# usb_serial.net
KiCad netlist of a schematic drawn in EAGLE
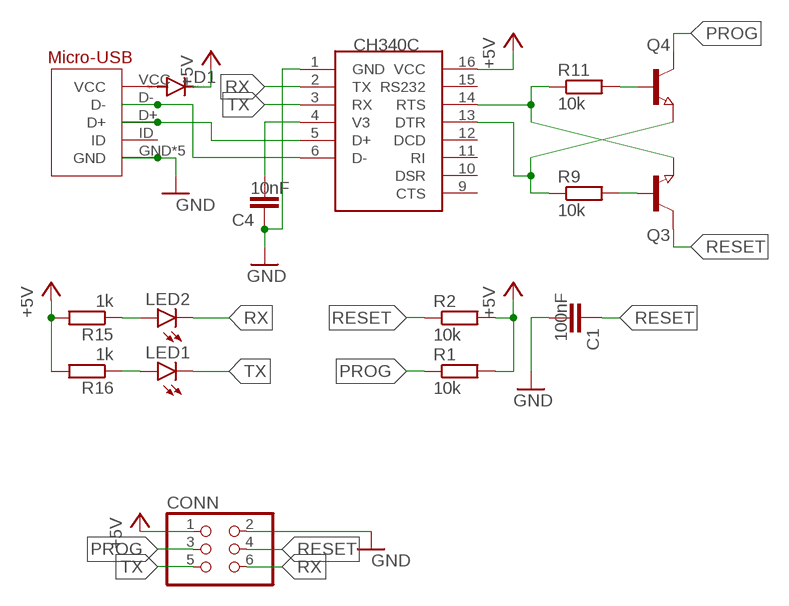
[diagram p0: schematic, sheet 1]

(export (version "E")
  (design (tool "Eeschema 10.0.6"))
  (components
    (comp (ref "C1")
      (value "100nF")
      (footprint "eagle-import:C0603K")
      (libsource (lib "eagle-import") (part "C-EUC0603K"))
    )
    (comp (ref "C4")
      (value "10nF")
      (footprint "eagle-import:C0603K")
      (libsource (lib "eagle-import") (part "C-EUC0603K"))
    )
    (comp (ref "CONN")
      (value "PINHD-2X3")
      (footprint "eagle-import:2X03")
      (libsource (lib "eagle-import") (part "PINHD-2X3"))
    )
    (comp (ref "D1")
      (value "DIODE-MICROMELF-R")
      (footprint "eagle-import:MICROMELF-R")
      (libsource (lib "eagle-import") (part "DIODE-MICROMELF-R"))
    )
    (comp (ref "J1")
      (value "MICRO-USB")
      (footprint "eagle-import:MICRO-USB")
      (fields
        (field (name "MANUFACTURER_PART_NUMBER") "ZX62D-B-5P8(30)")
        (field (name "COPYRIGHT") "Copyright (C) 2018 Accelerated Designs. All rights reserved")
      )
      (libsource (lib "eagle-import") (part "MICRO-USB"))
    )
    (comp (ref "LED1")
      (value "LEDCHIPLED_0805")
      (footprint "eagle-import:CHIPLED_0805")
      (libsource (lib "eagle-import") (part "LEDCHIPLED_0805"))
    )
    (comp (ref "LED2")
      (value "LEDCHIPLED_0805")
      (footprint "eagle-import:CHIPLED_0805")
      (libsource (lib "eagle-import") (part "LEDCHIPLED_0805"))
    )
    (comp (ref "Q3")
      (value "NPN-TRANSISTOR_SOT23")
      (footprint "eagle-import:SOT23")
      (libsource (lib "eagle-import") (part "NPN-TRANSISTOR_SOT23"))
    )
    (comp (ref "Q4")
      (value "NPN-TRANSISTOR_SOT23")
      (footprint "eagle-import:SOT23")
      (libsource (lib "eagle-import") (part "NPN-TRANSISTOR_SOT23"))
    )
    (comp (ref "R1")
      (value "10k")
      (footprint "eagle-import:R0603")
      (libsource (lib "eagle-import") (part "R-EU_R0603"))
    )
    (comp (ref "R2")
      (value "10k")
      (footprint "eagle-import:R0603")
      (libsource (lib "eagle-import") (part "R-EU_R0603"))
    )
    (comp (ref "R9")
      (value "10k")
      (footprint "eagle-import:R0603")
      (libsource (lib "eagle-import") (part "R-EU_R0603"))
    )
    (comp (ref "R11")
      (value "10k")
      (footprint "eagle-import:R0603")
      (libsource (lib "eagle-import") (part "R-EU_R0603"))
    )
    (comp (ref "R15")
      (value "1k")
      (footprint "eagle-import:R0603")
      (libsource (lib "eagle-import") (part "R-EU_R0603"))
    )
    (comp (ref "R16")
      (value "1k")
      (footprint "eagle-import:R0603")
      (libsource (lib "eagle-import") (part "R-EU_R0603"))
    )
    (comp (ref "U$3")
      (value "CH340C")
      (footprint "eagle-import:SOIC16")
      (libsource (lib "eagle-import") (part "CH340C"))
    )
  )
  (nets
    (net (code "1") (name "+5V") (class "Default")
      (node (ref "CONN") (pin "1") (pinfunction "1_1") (pintype "passive"))
      (node (ref "D1") (pin "C") (pinfunction "C_C") (pintype "passive"))
      (node (ref "R1") (pin "2") (pinfunction "2_2") (pintype "passive"))
      (node (ref "R15") (pin "2") (pinfunction "2_2") (pintype "passive"))
      (node (ref "R16") (pin "2") (pinfunction "2_2") (pintype "passive"))
      (node (ref "R2") (pin "2") (pinfunction "2_2") (pintype "passive"))
      (node (ref "U$3") (pin "16") (pinfunction "VCC_16") (pintype "bidirectional"))
    )
    (net (code "2") (name "GND") (class "Default")
      (node (ref "C1") (pin "2") (pinfunction "2_2") (pintype "passive"))
      (node (ref "C4") (pin "1") (pinfunction "1_1") (pintype "passive"))
      (node (ref "CONN") (pin "2") (pinfunction "2_2") (pintype "passive"))
      (node (ref "J1") (pin "GND") (pinfunction "GND_GND") (pintype "passive"))
      (node (ref "J1") (pin "GP1") (pinfunction "GND_GP1") (pintype "passive"))
      (node (ref "J1") (pin "GP2") (pinfunction "GND_GP2") (pintype "passive"))
      (node (ref "J1") (pin "GP3") (pinfunction "GND_GP3") (pintype "passive"))
      (node (ref "J1") (pin "GP4") (pinfunction "GND_GP4") (pintype "passive"))
      (node (ref "U$3") (pin "1") (pinfunction "GND_1") (pintype "bidirectional"))
    )
    (net (code "3") (name "Net-(D1-PadA)") (class "Default")
      (node (ref "D1") (pin "A") (pinfunction "A_A") (pintype "passive"))
      (node (ref "J1") (pin "VCC") (pinfunction "VCC_VCC") (pintype "passive"))
    )
    (net (code "4") (name "Net-(LED1-PadA)") (class "Default")
      (node (ref "LED1") (pin "A") (pinfunction "A_A") (pintype "passive"))
      (node (ref "R16") (pin "1") (pinfunction "1_1") (pintype "passive"))
    )
    (net (code "5") (name "Net-(LED2-PadA)") (class "Default")
      (node (ref "LED2") (pin "A") (pinfunction "A_A") (pintype "passive"))
      (node (ref "R15") (pin "1") (pinfunction "1_1") (pintype "passive"))
    )
    (net (code "6") (name "Net-(Q3-B)") (class "Default")
      (node (ref "Q3") (pin "1") (pinfunction "B_1") (pintype "passive"))
      (node (ref "R9") (pin "2") (pinfunction "2_2") (pintype "passive"))
    )
    (net (code "7") (name "Net-(Q3-E)") (class "Default")
      (node (ref "Q3") (pin "2") (pinfunction "E_2") (pintype "passive"))
      (node (ref "R11") (pin "1") (pinfunction "1_1") (pintype "passive"))
      (node (ref "U$3") (pin "14") (pinfunction "RTS_14") (pintype "bidirectional"))
    )
    (net (code "8") (name "Net-(Q4-B)") (class "Default")
      (node (ref "Q4") (pin "1") (pinfunction "B_1") (pintype "passive"))
      (node (ref "R11") (pin "2") (pinfunction "2_2") (pintype "passive"))
    )
    (net (code "9") (name "Net-(Q4-E)") (class "Default")
      (node (ref "Q4") (pin "2") (pinfunction "E_2") (pintype "passive"))
      (node (ref "R9") (pin "1") (pinfunction "1_1") (pintype "passive"))
      (node (ref "U$3") (pin "13") (pinfunction "DTR_13") (pintype "bidirectional"))
    )
    (net (code "10") (name "Net-(U$3-D+)") (class "Default")
      (node (ref "J1") (pin "D+") (pinfunction "D+_D+") (pintype "passive"))
      (node (ref "U$3") (pin "5") (pinfunction "D+_5") (pintype "bidirectional"))
    )
    (net (code "11") (name "Net-(U$3-D-)") (class "Default")
      (node (ref "J1") (pin "D-") (pinfunction "D-_D-") (pintype "passive"))
      (node (ref "U$3") (pin "6") (pinfunction "D-_6") (pintype "bidirectional"))
    )
    (net (code "12") (name "Net-(U$3-V3)") (class "Default")
      (node (ref "C4") (pin "2") (pinfunction "2_2") (pintype "passive"))
      (node (ref "U$3") (pin "4") (pinfunction "V3_4") (pintype "bidirectional"))
    )
    (net (code "13") (name "PROG") (class "Default")
      (node (ref "CONN") (pin "3") (pinfunction "3_3") (pintype "passive"))
      (node (ref "Q4") (pin "3") (pinfunction "C_3") (pintype "passive"))
      (node (ref "R1") (pin "1") (pinfunction "1_1") (pintype "passive"))
    )
    (net (code "14") (name "RESET") (class "Default")
      (node (ref "C1") (pin "1") (pinfunction "1_1") (pintype "passive"))
      (node (ref "CONN") (pin "4") (pinfunction "4_4") (pintype "passive"))
      (node (ref "Q3") (pin "3") (pinfunction "C_3") (pintype "passive"))
      (node (ref "R2") (pin "1") (pinfunction "1_1") (pintype "passive"))
    )
    (net (code "15") (name "RX") (class "Default")
      (node (ref "CONN") (pin "6") (pinfunction "6_6") (pintype "passive"))
      (node (ref "LED2") (pin "C") (pinfunction "C_C") (pintype "passive"))
      (node (ref "U$3") (pin "2") (pinfunction "TX_2") (pintype "bidirectional"))
    )
    (net (code "16") (name "TX") (class "Default")
      (node (ref "CONN") (pin "5") (pinfunction "5_5") (pintype "passive"))
      (node (ref "LED1") (pin "C") (pinfunction "C_C") (pintype "passive"))
      (node (ref "U$3") (pin "3") (pinfunction "RX_3") (pintype "bidirectional"))
    )
    (net (code "17") (name "unconnected-(J1-PadID)") (class "Default")
      (node (ref "J1") (pin "ID") (pinfunction "ID_ID") (pintype "passive"))
    )
    (net (code "18") (name "unconnected-(U$3-CTS-Pad9)") (class "Default")
      (node (ref "U$3") (pin "9") (pinfunction "CTS_9") (pintype "bidirectional"))
    )
    (net (code "19") (name "unconnected-(U$3-DCD-Pad12)") (class "Default")
      (node (ref "U$3") (pin "12") (pinfunction "DCD_12") (pintype "bidirectional"))
    )
    (net (code "20") (name "unconnected-(U$3-DSR-Pad10)") (class "Default")
      (node (ref "U$3") (pin "10") (pinfunction "DSR_10") (pintype "bidirectional"))
    )
    (net (code "21") (name "unconnected-(U$3-RI-Pad11)") (class "Default")
      (node (ref "U$3") (pin "11") (pinfunction "RI_11") (pintype "bidirectional"))
    )
    (net (code "22") (name "unconnected-(U$3-RS232-Pad15)") (class "Default")
      (node (ref "U$3") (pin "15") (pinfunction "RS232_15") (pintype "bidirectional"))
    )
  )
)
